# LCD_Cape.net
KiCad netlist of a schematic drawn in Altium Designer
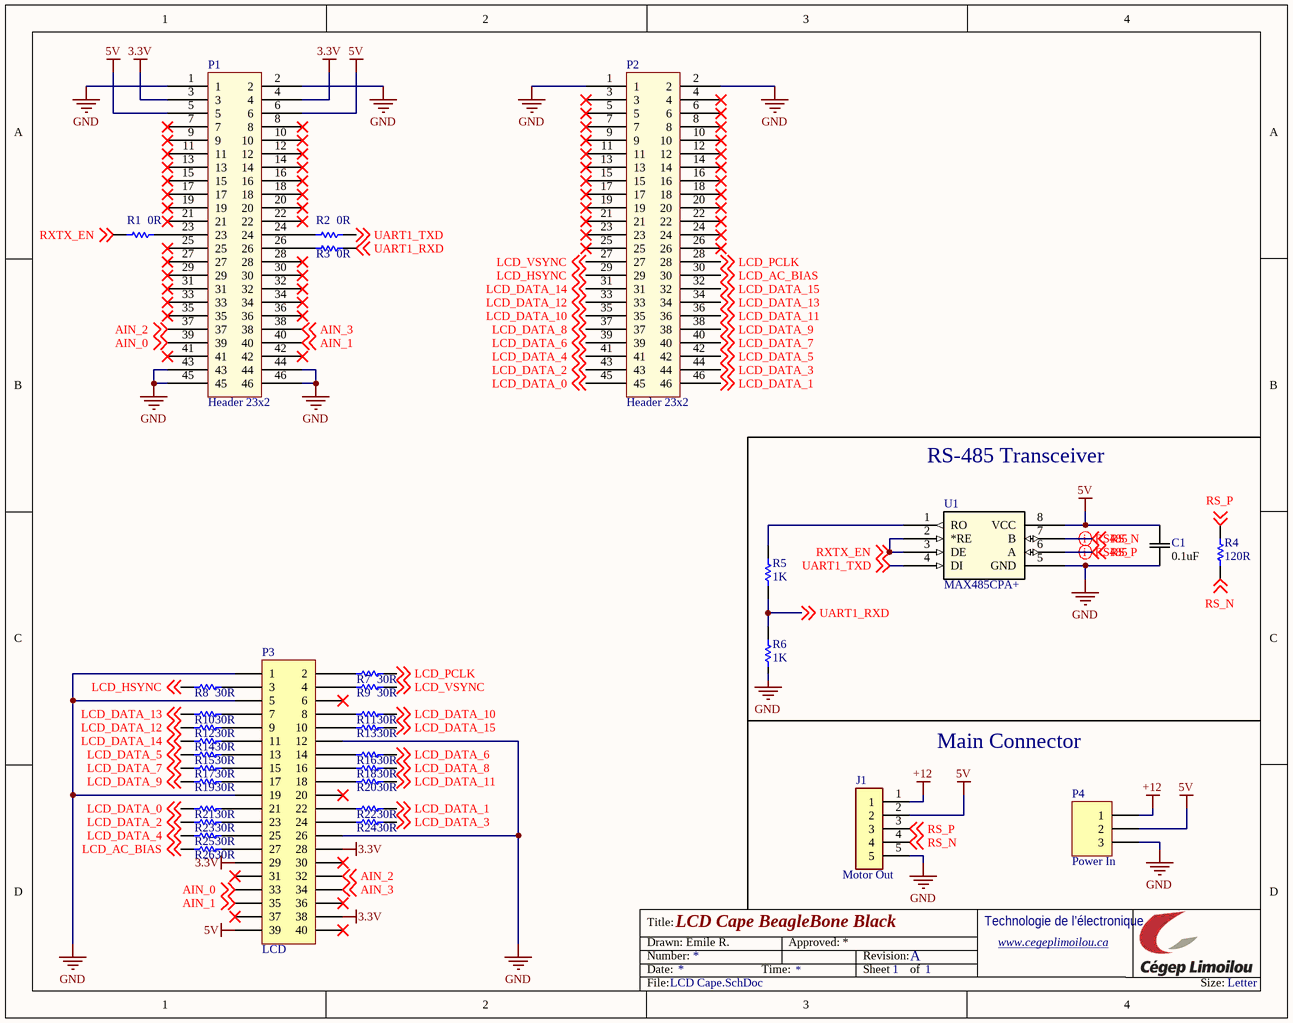
[diagram p0: LCD Cape.SchDoc]

(export (version "E")
  (design (tool "Eeschema 10.0.6"))
  (components
    (comp (ref "C1")
      (value "0.1uF")
      (footprint "C1206")
      (description "Capacitor SMD 1206")
      (fields
        (field (name "MANUFACTURER_PART_NUMBER") "12065A820JAT2A")
        (field (name "Comment") "Capacitor 1206")
        (field (name "COPYRIGHT") "Copyright (C) 2018 Accelerated Designs. All rights reserved")
      )
      (libsource (lib "Schematic_Emile") (part "Capacitor 1206"))
    )
    (comp (ref "J1")
      (value "Motor Out")
      (footprint "JST 5POS 2.5mm 90°")
      (description "Connector")
      (fields (field (name "MANUFACTURER_PART_NUMBER") "S5B-XH-A-1(LF)(SN)"))
      (libsource (lib "Schematic_Emile") (part "JST 5POS"))
    )
    (comp (ref "P1")
      (value "Header 23x2")
      (footprint "Header 23x2")
      (libsource (lib "Schematic_Emile") (part "Header 23x2"))
    )
    (comp (ref "P2")
      (value "Header 23x2")
      (footprint "Header 23x2")
      (libsource (lib "Schematic_Emile") (part "Header 23x2"))
    )
    (comp (ref "P3")
      (value "LCD")
      (footprint "HDR2X20")
      (description "Header, 20-Pin, Dual row")
      (fields (field (name "PUBLISHER") "Altium Limited"))
      (libsource (lib "Miscellaneous Connectors") (part "Header 20X2"))
    )
    (comp (ref "P4")
      (value "Power In")
      (footprint "Weco 3")
      (description "Header, 3-Pin")
      (fields (field (name "PUBLISHER") "Altium Limited"))
      (libsource (lib "Miscellaneous Connectors") (part "Header 3"))
    )
    (comp (ref "R1")
      (value "0R")
      (footprint "C1206")
      (description "Resistor")
      (fields (field (name "Comment") "Res1") (field (name "PUBLISHER") "Altium Limited"))
      (libsource (lib "Miscellaneous Devices") (part "Res1"))
    )
    (comp (ref "R2")
      (value "0R")
      (footprint "C1206")
      (description "Resistor")
      (fields (field (name "Comment") "Res1") (field (name "PUBLISHER") "Altium Limited"))
      (libsource (lib "Miscellaneous Devices") (part "Res1"))
    )
    (comp (ref "R3")
      (value "0R")
      (footprint "C1206")
      (description "Resistor")
      (fields (field (name "Comment") "Res1") (field (name "PUBLISHER") "Altium Limited"))
      (libsource (lib "Miscellaneous Devices") (part "Res1"))
    )
    (comp (ref "R4")
      (value "120R")
      (footprint "C1206")
      (description "Resistor")
      (fields (field (name "Comment") "Res1") (field (name "PUBLISHER") "Altium Limited"))
      (libsource (lib "Miscellaneous Devices") (part "Res1"))
    )
    (comp (ref "R5")
      (value "1K")
      (footprint "C1206")
      (description "Resistor")
      (fields (field (name "Comment") "Res1") (field (name "PUBLISHER") "Altium Limited"))
      (libsource (lib "Miscellaneous Devices") (part "Res1"))
    )
    (comp (ref "R6")
      (value "1K")
      (footprint "C1206")
      (description "Resistor")
      (fields (field (name "Comment") "Res1") (field (name "PUBLISHER") "Altium Limited"))
      (libsource (lib "Miscellaneous Devices") (part "Res1"))
    )
    (comp (ref "R7")
      (value "30R")
      (footprint "C1206")
      (description "Resistor")
      (fields (field (name "Comment") "Res1") (field (name "PUBLISHER") "Altium Limited"))
      (libsource (lib "Miscellaneous Devices") (part "Res1"))
    )
    (comp (ref "R8")
      (value "30R")
      (footprint "C1206")
      (description "Resistor")
      (fields (field (name "Comment") "Res1") (field (name "PUBLISHER") "Altium Limited"))
      (libsource (lib "Miscellaneous Devices") (part "Res1"))
    )
    (comp (ref "R9")
      (value "30R")
      (footprint "C1206")
      (description "Resistor")
      (fields (field (name "Comment") "Res1") (field (name "PUBLISHER") "Altium Limited"))
      (libsource (lib "Miscellaneous Devices") (part "Res1"))
    )
    (comp (ref "R10")
      (value "30R")
      (footprint "C1206")
      (description "Resistor")
      (fields (field (name "Comment") "Res1") (field (name "PUBLISHER") "Altium Limited"))
      (libsource (lib "Miscellaneous Devices") (part "Res1"))
    )
    (comp (ref "R11")
      (value "30R")
      (footprint "C1206")
      (description "Resistor")
      (fields (field (name "Comment") "Res1") (field (name "PUBLISHER") "Altium Limited"))
      (libsource (lib "Miscellaneous Devices") (part "Res1"))
    )
    (comp (ref "R12")
      (value "30R")
      (footprint "C1206")
      (description "Resistor")
      (fields (field (name "Comment") "Res1") (field (name "PUBLISHER") "Altium Limited"))
      (libsource (lib "Miscellaneous Devices") (part "Res1"))
    )
    (comp (ref "R13")
      (value "30R")
      (footprint "C1206")
      (description "Resistor")
      (fields (field (name "Comment") "Res1") (field (name "PUBLISHER") "Altium Limited"))
      (libsource (lib "Miscellaneous Devices") (part "Res1"))
    )
    (comp (ref "R14")
      (value "30R")
      (footprint "C1206")
      (description "Resistor")
      (fields (field (name "Comment") "Res1") (field (name "PUBLISHER") "Altium Limited"))
      (libsource (lib "Miscellaneous Devices") (part "Res1"))
    )
    (comp (ref "R15")
      (value "30R")
      (footprint "C1206")
      (description "Resistor")
      (fields (field (name "Comment") "Res1") (field (name "PUBLISHER") "Altium Limited"))
      (libsource (lib "Miscellaneous Devices") (part "Res1"))
    )
    (comp (ref "R16")
      (value "30R")
      (footprint "C1206")
      (description "Resistor")
      (fields (field (name "Comment") "Res1") (field (name "PUBLISHER") "Altium Limited"))
      (libsource (lib "Miscellaneous Devices") (part "Res1"))
    )
    (comp (ref "R17")
      (value "30R")
      (footprint "C1206")
      (description "Resistor")
      (fields (field (name "Comment") "Res1") (field (name "PUBLISHER") "Altium Limited"))
      (libsource (lib "Miscellaneous Devices") (part "Res1"))
    )
    (comp (ref "R18")
      (value "30R")
      (footprint "C1206")
      (description "Resistor")
      (fields (field (name "Comment") "Res1") (field (name "PUBLISHER") "Altium Limited"))
      (libsource (lib "Miscellaneous Devices") (part "Res1"))
    )
    (comp (ref "R19")
      (value "30R")
      (footprint "C1206")
      (description "Resistor")
      (fields (field (name "Comment") "Res1") (field (name "PUBLISHER") "Altium Limited"))
      (libsource (lib "Miscellaneous Devices") (part "Res1"))
    )
    (comp (ref "R20")
      (value "30R")
      (footprint "C1206")
      (description "Resistor")
      (fields (field (name "Comment") "Res1") (field (name "PUBLISHER") "Altium Limited"))
      (libsource (lib "Miscellaneous Devices") (part "Res1"))
    )
    (comp (ref "R21")
      (value "30R")
      (footprint "C1206")
      (description "Resistor")
      (fields (field (name "Comment") "Res1") (field (name "PUBLISHER") "Altium Limited"))
      (libsource (lib "Miscellaneous Devices") (part "Res1"))
    )
    (comp (ref "R22")
      (value "30R")
      (footprint "C1206")
      (description "Resistor")
      (fields (field (name "Comment") "Res1") (field (name "PUBLISHER") "Altium Limited"))
      (libsource (lib "Miscellaneous Devices") (part "Res1"))
    )
    (comp (ref "R23")
      (value "30R")
      (footprint "C1206")
      (description "Resistor")
      (fields (field (name "Comment") "Res1") (field (name "PUBLISHER") "Altium Limited"))
      (libsource (lib "Miscellaneous Devices") (part "Res1"))
    )
    (comp (ref "R24")
      (value "30R")
      (footprint "C1206")
      (description "Resistor")
      (fields (field (name "Comment") "Res1") (field (name "PUBLISHER") "Altium Limited"))
      (libsource (lib "Miscellaneous Devices") (part "Res1"))
    )
    (comp (ref "R25")
      (value "30R")
      (footprint "C1206")
      (description "Resistor")
      (fields (field (name "Comment") "Res1") (field (name "PUBLISHER") "Altium Limited"))
      (libsource (lib "Miscellaneous Devices") (part "Res1"))
    )
    (comp (ref "R26")
      (value "30R")
      (footprint "C1206")
      (description "Resistor")
      (fields (field (name "Comment") "Res1") (field (name "PUBLISHER") "Altium Limited"))
      (libsource (lib "Miscellaneous Devices") (part "Res1"))
    )
    (comp (ref "U1")
      (value "MAX485CPA+")
      (footprint "DIP 8 - 3D")
      (description "RS485 Communication")
      (fields (field (name "COPYRIGHT") "Copyright (C) 2018 Accelerated Designs. All rights reserved"))
      (libsource (lib "Schematic_Emile") (part "MAX485CPA+"))
    )
  )
  (nets
    (net (code "1") (name "+12") (class "Default")
      (node (ref "J1") (pin "1") (pinfunction "1_1") (pintype "passive"))
      (node (ref "P4") (pin "1") (pinfunction "1_1") (pintype "passive"))
    )
    (net (code "2") (name "3.3V") (class "Default")
      (node (ref "P1") (pin "3") (pinfunction "3_3") (pintype "passive"))
      (node (ref "P1") (pin "4") (pinfunction "4_4") (pintype "passive"))
      (node (ref "P3") (pin "28") (pinfunction "28_28") (pintype "passive"))
      (node (ref "P3") (pin "29") (pinfunction "29_29") (pintype "passive"))
      (node (ref "P3") (pin "38") (pinfunction "38_38") (pintype "passive"))
    )
    (net (code "3") (name "5V") (class "Default")
      (node (ref "C1") (pin "2") (pinfunction "2_2") (pintype "passive"))
      (node (ref "J1") (pin "2") (pinfunction "2_2") (pintype "passive"))
      (node (ref "P1") (pin "5") (pinfunction "5_5") (pintype "passive"))
      (node (ref "P1") (pin "6") (pinfunction "6_6") (pintype "passive"))
      (node (ref "P3") (pin "39") (pinfunction "39_39") (pintype "passive"))
      (node (ref "P4") (pin "2") (pinfunction "2_2") (pintype "passive"))
      (node (ref "U1") (pin "8") (pinfunction "VCC_8") (pintype "power_in"))
    )
    (net (code "4") (name "AIN_0") (class "Default")
      (node (ref "P1") (pin "39") (pinfunction "39_39") (pintype "passive"))
      (node (ref "P3") (pin "33") (pinfunction "33_33") (pintype "passive"))
    )
    (net (code "5") (name "AIN_1") (class "Default")
      (node (ref "P1") (pin "40") (pinfunction "40_40") (pintype "passive"))
      (node (ref "P3") (pin "35") (pinfunction "35_35") (pintype "passive"))
    )
    (net (code "6") (name "AIN_2") (class "Default")
      (node (ref "P1") (pin "37") (pinfunction "37_37") (pintype "passive"))
      (node (ref "P3") (pin "32") (pinfunction "32_32") (pintype "passive"))
    )
    (net (code "7") (name "AIN_3") (class "Default")
      (node (ref "P1") (pin "38") (pinfunction "38_38") (pintype "passive"))
      (node (ref "P3") (pin "34") (pinfunction "34_34") (pintype "passive"))
    )
    (net (code "8") (name "GND") (class "Default")
      (node (ref "C1") (pin "1") (pinfunction "1_1") (pintype "passive"))
      (node (ref "J1") (pin "5") (pinfunction "5_5") (pintype "passive"))
      (node (ref "P1") (pin "1") (pinfunction "1_1") (pintype "passive"))
      (node (ref "P1") (pin "2") (pinfunction "2_2") (pintype "passive"))
      (node (ref "P1") (pin "43") (pinfunction "43_43") (pintype "passive"))
      (node (ref "P1") (pin "44") (pinfunction "44_44") (pintype "passive"))
      (node (ref "P1") (pin "45") (pinfunction "45_45") (pintype "passive"))
      (node (ref "P1") (pin "46") (pinfunction "46_46") (pintype "passive"))
      (node (ref "P2") (pin "1") (pinfunction "1_1") (pintype "passive"))
      (node (ref "P2") (pin "2") (pinfunction "2_2") (pintype "passive"))
      (node (ref "P3") (pin "1") (pinfunction "1_1") (pintype "passive"))
      (node (ref "P3") (pin "12") (pinfunction "12_12") (pintype "passive"))
      (node (ref "P3") (pin "19") (pinfunction "19_19") (pintype "passive"))
      (node (ref "P3") (pin "26") (pinfunction "26_26") (pintype "passive"))
      (node (ref "P3") (pin "5") (pinfunction "5_5") (pintype "passive"))
      (node (ref "P4") (pin "3") (pinfunction "3_3") (pintype "passive"))
      (node (ref "R6") (pin "2") (pinfunction "2_2") (pintype "passive"))
      (node (ref "U1") (pin "5") (pinfunction "GND_5") (pintype "power_in"))
    )
    (net (code "9") (name "LCD_AC_BIAS") (class "Default")
      (node (ref "P2") (pin "30") (pinfunction "30_30") (pintype "passive"))
      (node (ref "R26") (pin "1") (pinfunction "1_1") (pintype "passive"))
    )
    (net (code "10") (name "LCD_DATA_0") (class "Default")
      (node (ref "P2") (pin "45") (pinfunction "45_45") (pintype "passive"))
      (node (ref "R21") (pin "1") (pinfunction "1_1") (pintype "passive"))
    )
    (net (code "11") (name "LCD_DATA_1") (class "Default")
      (node (ref "P2") (pin "46") (pinfunction "46_46") (pintype "passive"))
      (node (ref "R22") (pin "2") (pinfunction "2_2") (pintype "passive"))
    )
    (net (code "12") (name "LCD_DATA_2") (class "Default")
      (node (ref "P2") (pin "43") (pinfunction "43_43") (pintype "passive"))
      (node (ref "R23") (pin "1") (pinfunction "1_1") (pintype "passive"))
    )
    (net (code "13") (name "LCD_DATA_3") (class "Default")
      (node (ref "P2") (pin "44") (pinfunction "44_44") (pintype "passive"))
      (node (ref "R24") (pin "2") (pinfunction "2_2") (pintype "passive"))
    )
    (net (code "14") (name "LCD_DATA_4") (class "Default")
      (node (ref "P2") (pin "41") (pinfunction "41_41") (pintype "passive"))
      (node (ref "R25") (pin "1") (pinfunction "1_1") (pintype "passive"))
    )
    (net (code "15") (name "LCD_DATA_5") (class "Default")
      (node (ref "P2") (pin "42") (pinfunction "42_42") (pintype "passive"))
      (node (ref "R15") (pin "1") (pinfunction "1_1") (pintype "passive"))
    )
    (net (code "16") (name "LCD_DATA_6") (class "Default")
      (node (ref "P2") (pin "39") (pinfunction "39_39") (pintype "passive"))
      (node (ref "R16") (pin "2") (pinfunction "2_2") (pintype "passive"))
    )
    (net (code "17") (name "LCD_DATA_7") (class "Default")
      (node (ref "P2") (pin "40") (pinfunction "40_40") (pintype "passive"))
      (node (ref "R17") (pin "1") (pinfunction "1_1") (pintype "passive"))
    )
    (net (code "18") (name "LCD_DATA_8") (class "Default")
      (node (ref "P2") (pin "37") (pinfunction "37_37") (pintype "passive"))
      (node (ref "R18") (pin "2") (pinfunction "2_2") (pintype "passive"))
    )
    (net (code "19") (name "LCD_DATA_9") (class "Default")
      (node (ref "P2") (pin "38") (pinfunction "38_38") (pintype "passive"))
      (node (ref "R19") (pin "1") (pinfunction "1_1") (pintype "passive"))
    )
    (net (code "20") (name "LCD_DATA_10") (class "Default")
      (node (ref "P2") (pin "35") (pinfunction "35_35") (pintype "passive"))
      (node (ref "R11") (pin "2") (pinfunction "2_2") (pintype "passive"))
    )
    (net (code "21") (name "LCD_DATA_11") (class "Default")
      (node (ref "P2") (pin "36") (pinfunction "36_36") (pintype "passive"))
      (node (ref "R20") (pin "2") (pinfunction "2_2") (pintype "passive"))
    )
    (net (code "22") (name "LCD_DATA_12") (class "Default")
      (node (ref "P2") (pin "33") (pinfunction "33_33") (pintype "passive"))
      (node (ref "R12") (pin "1") (pinfunction "1_1") (pintype "passive"))
    )
    (net (code "23") (name "LCD_DATA_13") (class "Default")
      (node (ref "P2") (pin "34") (pinfunction "34_34") (pintype "passive"))
      (node (ref "R10") (pin "1") (pinfunction "1_1") (pintype "passive"))
    )
    (net (code "24") (name "LCD_DATA_14") (class "Default")
      (node (ref "P2") (pin "31") (pinfunction "31_31") (pintype "passive"))
      (node (ref "R14") (pin "1") (pinfunction "1_1") (pintype "passive"))
    )
    (net (code "25") (name "LCD_DATA_15") (class "Default")
      (node (ref "P2") (pin "32") (pinfunction "32_32") (pintype "passive"))
      (node (ref "R13") (pin "2") (pinfunction "2_2") (pintype "passive"))
    )
    (net (code "26") (name "LCD_HSYNC") (class "Default")
      (node (ref "P2") (pin "29") (pinfunction "29_29") (pintype "passive"))
      (node (ref "R8") (pin "1") (pinfunction "1_1") (pintype "passive"))
    )
    (net (code "27") (name "LCD_PCLK") (class "Default")
      (node (ref "P2") (pin "28") (pinfunction "28_28") (pintype "passive"))
      (node (ref "R7") (pin "2") (pinfunction "2_2") (pintype "passive"))
    )
    (net (code "28") (name "LCD_VSYNC") (class "Default")
      (node (ref "P2") (pin "27") (pinfunction "27_27") (pintype "passive"))
      (node (ref "R9") (pin "2") (pinfunction "2_2") (pintype "passive"))
    )
    (net (code "29") (name "Net-(P1-Pad23)") (class "Default")
      (node (ref "P1") (pin "23") (pinfunction "23_23") (pintype "passive"))
      (node (ref "R1") (pin "2") (pinfunction "2_2") (pintype "passive"))
    )
    (net (code "30") (name "Net-(P1-Pad24)") (class "Default")
      (node (ref "P1") (pin "24") (pinfunction "24_24") (pintype "passive"))
      (node (ref "R2") (pin "1") (pinfunction "1_1") (pintype "passive"))
    )
    (net (code "31") (name "Net-(P1-Pad26)") (class "Default")
      (node (ref "P1") (pin "26") (pinfunction "26_26") (pintype "passive"))
      (node (ref "R3") (pin "1") (pinfunction "1_1") (pintype "passive"))
    )
    (net (code "32") (name "Net-(P3-Pad2)") (class "Default")
      (node (ref "P3") (pin "2") (pinfunction "2_2") (pintype "passive"))
      (node (ref "R7") (pin "1") (pinfunction "1_1") (pintype "passive"))
    )
    (net (code "33") (name "Net-(P3-Pad3)") (class "Default")
      (node (ref "P3") (pin "3") (pinfunction "3_3") (pintype "passive"))
      (node (ref "R8") (pin "2") (pinfunction "2_2") (pintype "passive"))
    )
    (net (code "34") (name "Net-(P3-Pad4)") (class "Default")
      (node (ref "P3") (pin "4") (pinfunction "4_4") (pintype "passive"))
      (node (ref "R9") (pin "1") (pinfunction "1_1") (pintype "passive"))
    )
    (net (code "35") (name "Net-(P3-Pad7)") (class "Default")
      (node (ref "P3") (pin "7") (pinfunction "7_7") (pintype "passive"))
      (node (ref "R10") (pin "2") (pinfunction "2_2") (pintype "passive"))
    )
    (net (code "36") (name "Net-(P3-Pad8)") (class "Default")
      (node (ref "P3") (pin "8") (pinfunction "8_8") (pintype "passive"))
      (node (ref "R11") (pin "1") (pinfunction "1_1") (pintype "passive"))
    )
    (net (code "37") (name "Net-(P3-Pad9)") (class "Default")
      (node (ref "P3") (pin "9") (pinfunction "9_9") (pintype "passive"))
      (node (ref "R12") (pin "2") (pinfunction "2_2") (pintype "passive"))
    )
    (net (code "38") (name "Net-(P3-Pad10)") (class "Default")
      (node (ref "P3") (pin "10") (pinfunction "10_10") (pintype "passive"))
      (node (ref "R13") (pin "1") (pinfunction "1_1") (pintype "passive"))
    )
    (net (code "39") (name "Net-(P3-Pad11)") (class "Default")
      (node (ref "P3") (pin "11") (pinfunction "11_11") (pintype "passive"))
      (node (ref "R14") (pin "2") (pinfunction "2_2") (pintype "passive"))
    )
    (net (code "40") (name "Net-(P3-Pad13)") (class "Default")
      (node (ref "P3") (pin "13") (pinfunction "13_13") (pintype "passive"))
      (node (ref "R15") (pin "2") (pinfunction "2_2") (pintype "passive"))
    )
    (net (code "41") (name "Net-(P3-Pad14)") (class "Default")
      (node (ref "P3") (pin "14") (pinfunction "14_14") (pintype "passive"))
      (node (ref "R16") (pin "1") (pinfunction "1_1") (pintype "passive"))
    )
    (net (code "42") (name "Net-(P3-Pad15)") (class "Default")
      (node (ref "P3") (pin "15") (pinfunction "15_15") (pintype "passive"))
      (node (ref "R17") (pin "2") (pinfunction "2_2") (pintype "passive"))
    )
    (net (code "43") (name "Net-(P3-Pad16)") (class "Default")
      (node (ref "P3") (pin "16") (pinfunction "16_16") (pintype "passive"))
      (node (ref "R18") (pin "1") (pinfunction "1_1") (pintype "passive"))
    )
    (net (code "44") (name "Net-(P3-Pad17)") (class "Default")
      (node (ref "P3") (pin "17") (pinfunction "17_17") (pintype "passive"))
      (node (ref "R19") (pin "2") (pinfunction "2_2") (pintype "passive"))
    )
    (net (code "45") (name "Net-(P3-Pad18)") (class "Default")
      (node (ref "P3") (pin "18") (pinfunction "18_18") (pintype "passive"))
      (node (ref "R20") (pin "1") (pinfunction "1_1") (pintype "passive"))
    )
    (net (code "46") (name "Net-(P3-Pad21)") (class "Default")
      (node (ref "P3") (pin "21") (pinfunction "21_21") (pintype "passive"))
      (node (ref "R21") (pin "2") (pinfunction "2_2") (pintype "passive"))
    )
    (net (code "47") (name "Net-(P3-Pad22)") (class "Default")
      (node (ref "P3") (pin "22") (pinfunction "22_22") (pintype "passive"))
      (node (ref "R22") (pin "1") (pinfunction "1_1") (pintype "passive"))
    )
    (net (code "48") (name "Net-(P3-Pad23)") (class "Default")
      (node (ref "P3") (pin "23") (pinfunction "23_23") (pintype "passive"))
      (node (ref "R23") (pin "2") (pinfunction "2_2") (pintype "passive"))
    )
    (net (code "49") (name "Net-(P3-Pad24)") (class "Default")
      (node (ref "P3") (pin "24") (pinfunction "24_24") (pintype "passive"))
      (node (ref "R24") (pin "1") (pinfunction "1_1") (pintype "passive"))
    )
    (net (code "50") (name "Net-(P3-Pad25)") (class "Default")
      (node (ref "P3") (pin "25") (pinfunction "25_25") (pintype "passive"))
      (node (ref "R25") (pin "2") (pinfunction "2_2") (pintype "passive"))
    )
    (net (code "51") (name "Net-(P3-Pad27)") (class "Default")
      (node (ref "P3") (pin "27") (pinfunction "27_27") (pintype "passive"))
      (node (ref "R26") (pin "2") (pinfunction "2_2") (pintype "passive"))
    )
    (net (code "52") (name "Net-(U1-RO)") (class "Default")
      (node (ref "R5") (pin "1") (pinfunction "1_1") (pintype "passive"))
      (node (ref "U1") (pin "1") (pinfunction "RO_1") (pintype "output"))
    )
    (net (code "53") (name "RS_N") (class "Default")
      (node (ref "J1") (pin "4") (pinfunction "4_4") (pintype "passive"))
      (node (ref "R4") (pin "2") (pinfunction "2_2") (pintype "passive"))
      (node (ref "U1") (pin "7") (pinfunction "B_7") (pintype "bidirectional"))
    )
    (net (code "54") (name "RS_P") (class "Default")
      (node (ref "J1") (pin "3") (pinfunction "3_3") (pintype "passive"))
      (node (ref "R4") (pin "1") (pinfunction "1_1") (pintype "passive"))
      (node (ref "U1") (pin "6") (pinfunction "A_6") (pintype "bidirectional"))
    )
    (net (code "55") (name "RXTX_EN") (class "Default")
      (node (ref "R1") (pin "1") (pinfunction "1_1") (pintype "passive"))
      (node (ref "U1") (pin "2") (pinfunction "*RE_2") (pintype "input"))
      (node (ref "U1") (pin "3") (pinfunction "DE_3") (pintype "input"))
    )
    (net (code "56") (name "UART1_RXD") (class "Default")
      (node (ref "R3") (pin "2") (pinfunction "2_2") (pintype "passive"))
      (node (ref "R5") (pin "2") (pinfunction "2_2") (pintype "passive"))
      (node (ref "R6") (pin "1") (pinfunction "1_1") (pintype "passive"))
    )
    (net (code "57") (name "UART1_TXD") (class "Default")
      (node (ref "R2") (pin "2") (pinfunction "2_2") (pintype "passive"))
      (node (ref "U1") (pin "4") (pinfunction "DI_4") (pintype "input"))
    )
    (net (code "58") (name "unconnected-(P1-Pad7)") (class "Default")
      (node (ref "P1") (pin "7") (pinfunction "7_7") (pintype "passive+no_connect"))
    )
    (net (code "59") (name "unconnected-(P1-Pad8)") (class "Default")
      (node (ref "P1") (pin "8") (pinfunction "8_8") (pintype "passive+no_connect"))
    )
    (net (code "60") (name "unconnected-(P1-Pad9)") (class "Default")
      (node (ref "P1") (pin "9") (pinfunction "9_9") (pintype "passive+no_connect"))
    )
    (net (code "61") (name "unconnected-(P1-Pad10)") (class "Default")
      (node (ref "P1") (pin "10") (pinfunction "10_10") (pintype "passive+no_connect"))
    )
    (net (code "62") (name "unconnected-(P1-Pad11)") (class "Default")
      (node (ref "P1") (pin "11") (pinfunction "11_11") (pintype "passive+no_connect"))
    )
    (net (code "63") (name "unconnected-(P1-Pad12)") (class "Default")
      (node (ref "P1") (pin "12") (pinfunction "12_12") (pintype "passive+no_connect"))
    )
    (net (code "64") (name "unconnected-(P1-Pad13)") (class "Default")
      (node (ref "P1") (pin "13") (pinfunction "13_13") (pintype "passive+no_connect"))
    )
    (net (code "65") (name "unconnected-(P1-Pad14)") (class "Default")
      (node (ref "P1") (pin "14") (pinfunction "14_14") (pintype "passive+no_connect"))
    )
    (net (code "66") (name "unconnected-(P1-Pad15)") (class "Default")
      (node (ref "P1") (pin "15") (pinfunction "15_15") (pintype "passive+no_connect"))
    )
    (net (code "67") (name "unconnected-(P1-Pad16)") (class "Default")
      (node (ref "P1") (pin "16") (pinfunction "16_16") (pintype "passive+no_connect"))
    )
    (net (code "68") (name "unconnected-(P1-Pad17)") (class "Default")
      (node (ref "P1") (pin "17") (pinfunction "17_17") (pintype "passive+no_connect"))
    )
    (net (code "69") (name "unconnected-(P1-Pad18)") (class "Default")
      (node (ref "P1") (pin "18") (pinfunction "18_18") (pintype "passive+no_connect"))
    )
    (net (code "70") (name "unconnected-(P1-Pad19)") (class "Default")
      (node (ref "P1") (pin "19") (pinfunction "19_19") (pintype "passive+no_connect"))
    )
    (net (code "71") (name "unconnected-(P1-Pad20)") (class "Default")
      (node (ref "P1") (pin "20") (pinfunction "20_20") (pintype "passive+no_connect"))
    )
    (net (code "72") (name "unconnected-(P1-Pad21)") (class "Default")
      (node (ref "P1") (pin "21") (pinfunction "21_21") (pintype "passive+no_connect"))
    )
    (net (code "73") (name "unconnected-(P1-Pad22)") (class "Default")
      (node (ref "P1") (pin "22") (pinfunction "22_22") (pintype "passive+no_connect"))
    )
    (net (code "74") (name "unconnected-(P1-Pad25)") (class "Default")
      (node (ref "P1") (pin "25") (pinfunction "25_25") (pintype "passive+no_connect"))
    )
    (net (code "75") (name "unconnected-(P1-Pad27)") (class "Default")
      (node (ref "P1") (pin "27") (pinfunction "27_27") (pintype "passive+no_connect"))
    )
    (net (code "76") (name "unconnected-(P1-Pad28)") (class "Default")
      (node (ref "P1") (pin "28") (pinfunction "28_28") (pintype "passive+no_connect"))
    )
    (net (code "77") (name "unconnected-(P1-Pad29)") (class "Default")
      (node (ref "P1") (pin "29") (pinfunction "29_29") (pintype "passive+no_connect"))
    )
    (net (code "78") (name "unconnected-(P1-Pad30)") (class "Default")
      (node (ref "P1") (pin "30") (pinfunction "30_30") (pintype "passive+no_connect"))
    )
    (net (code "79") (name "unconnected-(P1-Pad31)") (class "Default")
      (node (ref "P1") (pin "31") (pinfunction "31_31") (pintype "passive+no_connect"))
    )
    (net (code "80") (name "unconnected-(P1-Pad32)") (class "Default")
      (node (ref "P1") (pin "32") (pinfunction "32_32") (pintype "passive+no_connect"))
    )
    (net (code "81") (name "unconnected-(P1-Pad33)") (class "Default")
      (node (ref "P1") (pin "33") (pinfunction "33_33") (pintype "passive+no_connect"))
    )
    (net (code "82") (name "unconnected-(P1-Pad34)") (class "Default")
      (node (ref "P1") (pin "34") (pinfunction "34_34") (pintype "passive+no_connect"))
    )
    (net (code "83") (name "unconnected-(P1-Pad35)") (class "Default")
      (node (ref "P1") (pin "35") (pinfunction "35_35") (pintype "passive+no_connect"))
    )
    (net (code "84") (name "unconnected-(P1-Pad36)") (class "Default")
      (node (ref "P1") (pin "36") (pinfunction "36_36") (pintype "passive+no_connect"))
    )
    (net (code "85") (name "unconnected-(P1-Pad41)") (class "Default")
      (node (ref "P1") (pin "41") (pinfunction "41_41") (pintype "passive+no_connect"))
    )
    (net (code "86") (name "unconnected-(P1-Pad42)") (class "Default")
      (node (ref "P1") (pin "42") (pinfunction "42_42") (pintype "passive+no_connect"))
    )
    (net (code "87") (name "unconnected-(P2-Pad3)") (class "Default")
      (node (ref "P2") (pin "3") (pinfunction "3_3") (pintype "passive+no_connect"))
    )
    (net (code "88") (name "unconnected-(P2-Pad4)") (class "Default")
      (node (ref "P2") (pin "4") (pinfunction "4_4") (pintype "passive+no_connect"))
    )
    (net (code "89") (name "unconnected-(P2-Pad5)") (class "Default")
      (node (ref "P2") (pin "5") (pinfunction "5_5") (pintype "passive+no_connect"))
    )
    (net (code "90") (name "unconnected-(P2-Pad6)") (class "Default")
      (node (ref "P2") (pin "6") (pinfunction "6_6") (pintype "passive+no_connect"))
    )
    (net (code "91") (name "unconnected-(P2-Pad7)") (class "Default")
      (node (ref "P2") (pin "7") (pinfunction "7_7") (pintype "passive+no_connect"))
    )
    (net (code "92") (name "unconnected-(P2-Pad8)") (class "Default")
      (node (ref "P2") (pin "8") (pinfunction "8_8") (pintype "passive+no_connect"))
    )
    (net (code "93") (name "unconnected-(P2-Pad9)") (class "Default")
      (node (ref "P2") (pin "9") (pinfunction "9_9") (pintype "passive+no_connect"))
    )
    (net (code "94") (name "unconnected-(P2-Pad10)") (class "Default")
      (node (ref "P2") (pin "10") (pinfunction "10_10") (pintype "passive+no_connect"))
    )
    (net (code "95") (name "unconnected-(P2-Pad11)") (class "Default")
      (node (ref "P2") (pin "11") (pinfunction "11_11") (pintype "passive+no_connect"))
    )
    (net (code "96") (name "unconnected-(P2-Pad12)") (class "Default")
      (node (ref "P2") (pin "12") (pinfunction "12_12") (pintype "passive+no_connect"))
    )
    (net (code "97") (name "unconnected-(P2-Pad13)") (class "Default")
      (node (ref "P2") (pin "13") (pinfunction "13_13") (pintype "passive+no_connect"))
    )
    (net (code "98") (name "unconnected-(P2-Pad14)") (class "Default")
      (node (ref "P2") (pin "14") (pinfunction "14_14") (pintype "passive+no_connect"))
    )
    (net (code "99") (name "unconnected-(P2-Pad15)") (class "Default")
      (node (ref "P2") (pin "15") (pinfunction "15_15") (pintype "passive+no_connect"))
    )
    (net (code "100") (name "unconnected-(P2-Pad16)") (class "Default")
      (node (ref "P2") (pin "16") (pinfunction "16_16") (pintype "passive+no_connect"))
    )
    (net (code "101") (name "unconnected-(P2-Pad17)") (class "Default")
      (node (ref "P2") (pin "17") (pinfunction "17_17") (pintype "passive+no_connect"))
    )
    (net (code "102") (name "unconnected-(P2-Pad18)") (class "Default")
      (node (ref "P2") (pin "18") (pinfunction "18_18") (pintype "passive+no_connect"))
    )
    (net (code "103") (name "unconnected-(P2-Pad19)") (class "Default")
      (node (ref "P2") (pin "19") (pinfunction "19_19") (pintype "passive+no_connect"))
    )
    (net (code "104") (name "unconnected-(P2-Pad20)") (class "Default")
      (node (ref "P2") (pin "20") (pinfunction "20_20") (pintype "passive+no_connect"))
    )
    (net (code "105") (name "unconnected-(P2-Pad21)") (class "Default")
      (node (ref "P2") (pin "21") (pinfunction "21_21") (pintype "passive+no_connect"))
    )
    (net (code "106") (name "unconnected-(P2-Pad22)") (class "Default")
      (node (ref "P2") (pin "22") (pinfunction "22_22") (pintype "passive+no_connect"))
    )
    (net (code "107") (name "unconnected-(P2-Pad23)") (class "Default")
      (node (ref "P2") (pin "23") (pinfunction "23_23") (pintype "passive+no_connect"))
    )
    (net (code "108") (name "unconnected-(P2-Pad24)") (class "Default")
      (node (ref "P2") (pin "24") (pinfunction "24_24") (pintype "passive+no_connect"))
    )
    (net (code "109") (name "unconnected-(P2-Pad25)") (class "Default")
      (node (ref "P2") (pin "25") (pinfunction "25_25") (pintype "passive+no_connect"))
    )
    (net (code "110") (name "unconnected-(P2-Pad26)") (class "Default")
      (node (ref "P2") (pin "26") (pinfunction "26_26") (pintype "passive+no_connect"))
    )
    (net (code "111") (name "unconnected-(P3-Pad6)") (class "Default")
      (node (ref "P3") (pin "6") (pinfunction "6_6") (pintype "passive+no_connect"))
    )
    (net (code "112") (name "unconnected-(P3-Pad20)") (class "Default")
      (node (ref "P3") (pin "20") (pinfunction "20_20") (pintype "passive+no_connect"))
    )
    (net (code "113") (name "unconnected-(P3-Pad30)") (class "Default")
      (node (ref "P3") (pin "30") (pinfunction "30_30") (pintype "passive+no_connect"))
    )
    (net (code "114") (name "unconnected-(P3-Pad31)") (class "Default")
      (node (ref "P3") (pin "31") (pinfunction "31_31") (pintype "passive+no_connect"))
    )
    (net (code "115") (name "unconnected-(P3-Pad36)") (class "Default")
      (node (ref "P3") (pin "36") (pinfunction "36_36") (pintype "passive+no_connect"))
    )
    (net (code "116") (name "unconnected-(P3-Pad37)") (class "Default")
      (node (ref "P3") (pin "37") (pinfunction "37_37") (pintype "passive+no_connect"))
    )
    (net (code "117") (name "unconnected-(P3-Pad40)") (class "Default")
      (node (ref "P3") (pin "40") (pinfunction "40_40") (pintype "passive+no_connect"))
    )
  )
)
